# 10BASE-T1L.net
KiCad netlist of a schematic drawn in EAGLE
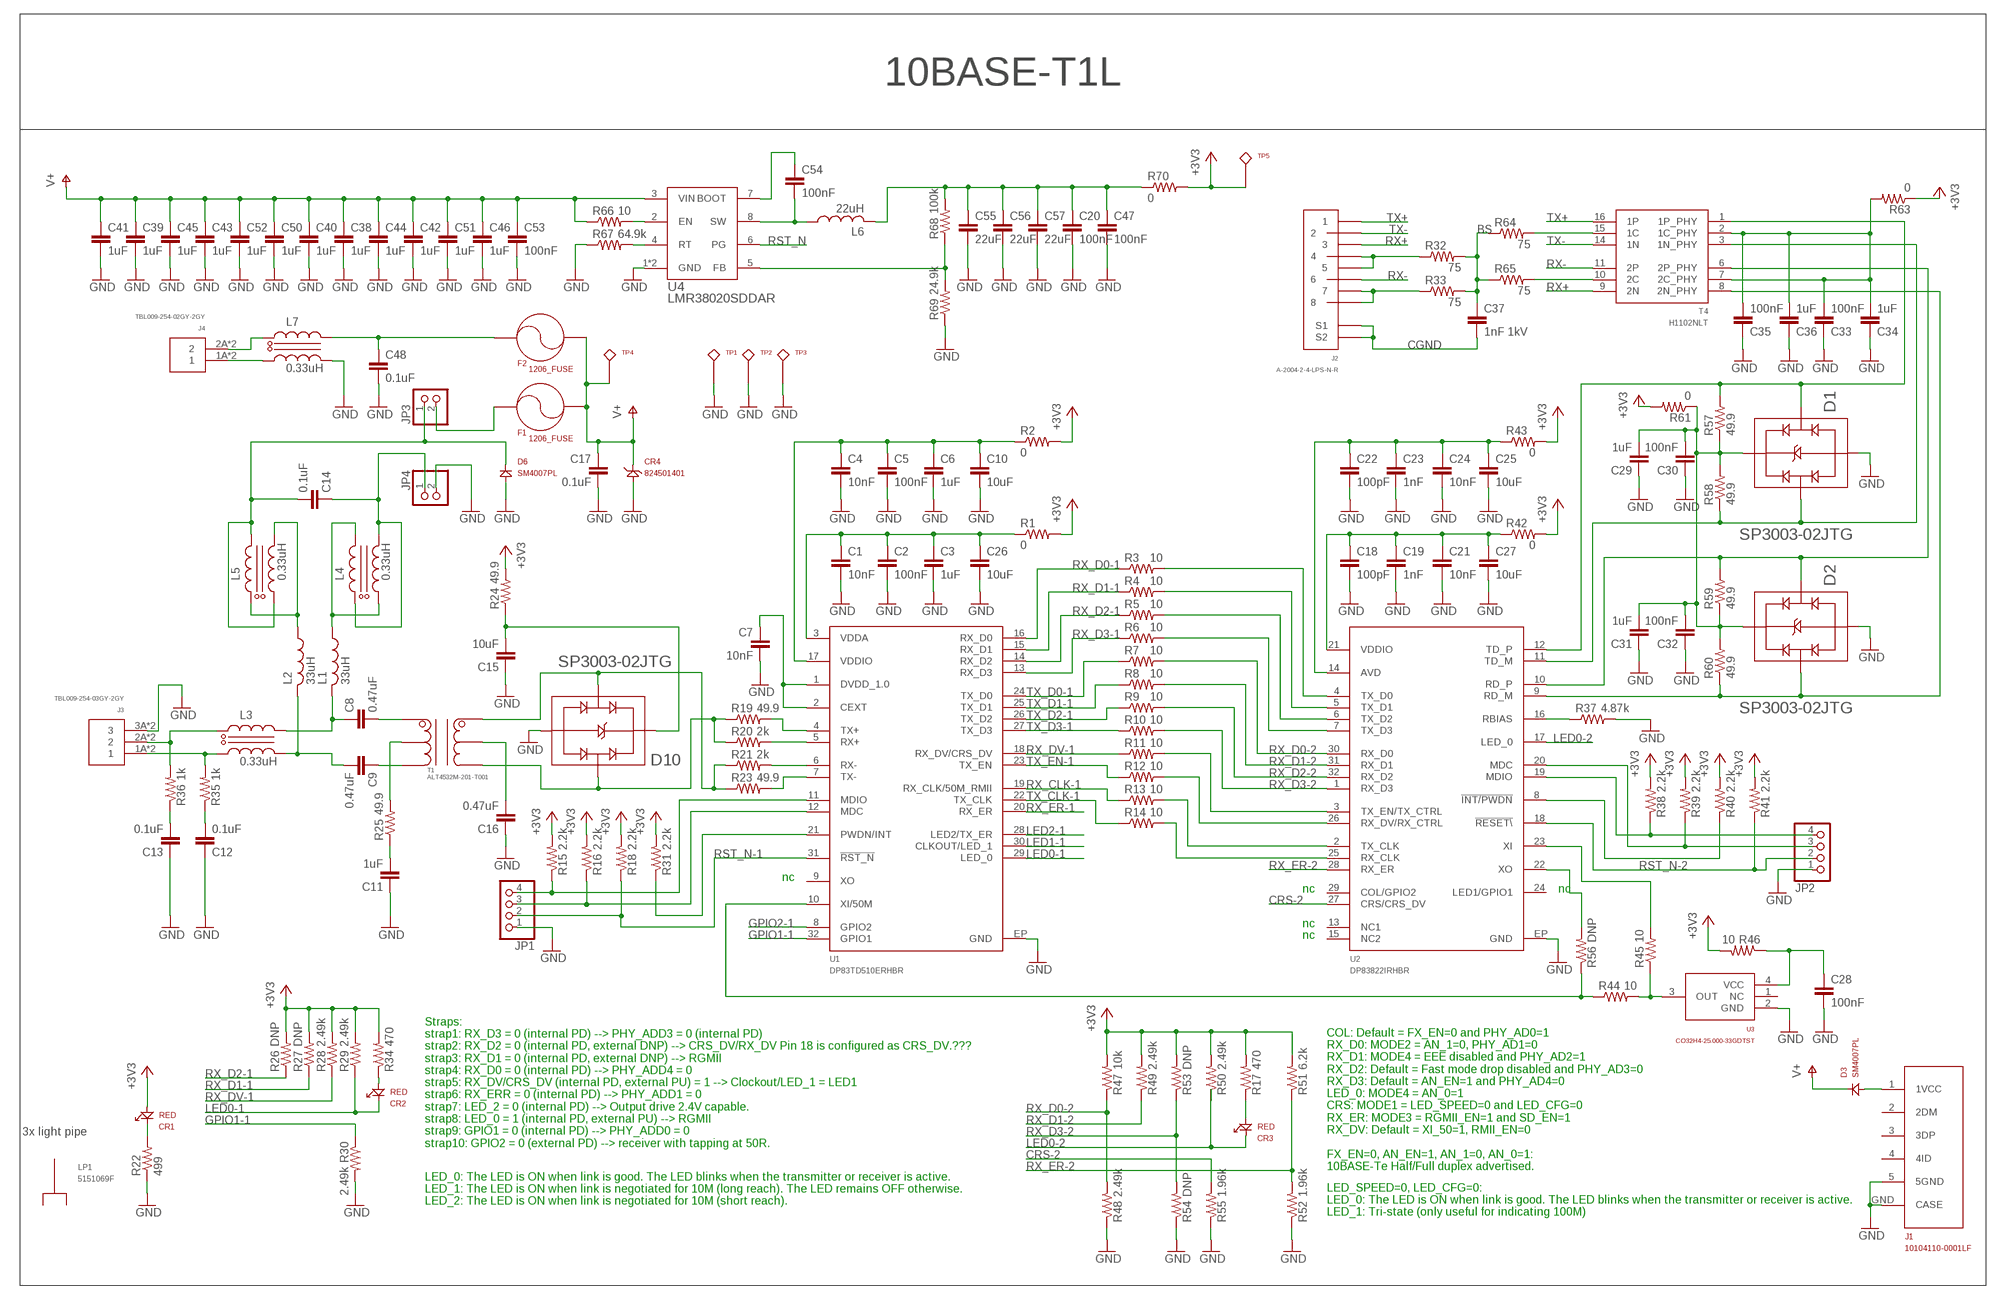
[diagram p0: schematic, sheet 1]

(export (version "E")
  (design (tool "Eeschema 10.0.6"))
  (components
    (comp (ref "C1")
      (value "10nF")
      (footprint "eagle-import:0603")
      (libsource (lib "eagle-import") (part "0603_CAPACITOR"))
    )
    (comp (ref "C2")
      (value "100nF")
      (footprint "eagle-import:0603")
      (libsource (lib "eagle-import") (part "0603_CAPACITOR"))
    )
    (comp (ref "C3")
      (value "1uF")
      (footprint "eagle-import:0603")
      (libsource (lib "eagle-import") (part "0603_CAPACITOR"))
    )
    (comp (ref "C4")
      (value "10nF")
      (footprint "eagle-import:0603")
      (libsource (lib "eagle-import") (part "0603_CAPACITOR"))
    )
    (comp (ref "C5")
      (value "100nF")
      (footprint "eagle-import:0603")
      (libsource (lib "eagle-import") (part "0603_CAPACITOR"))
    )
    (comp (ref "C6")
      (value "1uF")
      (footprint "eagle-import:0603")
      (libsource (lib "eagle-import") (part "0603_CAPACITOR"))
    )
    (comp (ref "C7")
      (value "10nF")
      (footprint "eagle-import:0603")
      (libsource (lib "eagle-import") (part "0603_CAPACITOR"))
    )
    (comp (ref "C8")
      (value "0.47uF")
      (footprint "eagle-import:0603")
      (libsource (lib "eagle-import") (part "0603_CAPACITOR"))
    )
    (comp (ref "C9")
      (value "0.47uF")
      (footprint "eagle-import:0603")
      (libsource (lib "eagle-import") (part "0603_CAPACITOR"))
    )
    (comp (ref "C10")
      (value "10uF")
      (footprint "eagle-import:0805")
      (libsource (lib "eagle-import") (part "0805_CAPACITOR"))
    )
    (comp (ref "C11")
      (value "1uF")
      (footprint "eagle-import:0603")
      (libsource (lib "eagle-import") (part "0603_CAPACITOR"))
    )
    (comp (ref "C12")
      (value "0.1uF")
      (footprint "eagle-import:0603")
      (libsource (lib "eagle-import") (part "0603_CAPACITOR"))
    )
    (comp (ref "C13")
      (value "0.1uF")
      (footprint "eagle-import:0603")
      (libsource (lib "eagle-import") (part "0603_CAPACITOR"))
    )
    (comp (ref "C14")
      (value "0.1uF")
      (footprint "eagle-import:0603")
      (libsource (lib "eagle-import") (part "0603_CAPACITOR"))
    )
    (comp (ref "C15")
      (value "10uF")
      (footprint "eagle-import:0603")
      (libsource (lib "eagle-import") (part "0603_CAPACITOR"))
    )
    (comp (ref "C16")
      (value "0.47uF")
      (footprint "eagle-import:0603")
      (libsource (lib "eagle-import") (part "0603_CAPACITOR"))
    )
    (comp (ref "C17")
      (value "0.1uF")
      (footprint "eagle-import:0603")
      (libsource (lib "eagle-import") (part "0603_CAPACITOR"))
    )
    (comp (ref "C18")
      (value "100pF")
      (footprint "eagle-import:0603")
      (libsource (lib "eagle-import") (part "0603_CAPACITOR"))
    )
    (comp (ref "C19")
      (value "1nF")
      (footprint "eagle-import:0603")
      (libsource (lib "eagle-import") (part "0603_CAPACITOR"))
    )
    (comp (ref "C20")
      (value "100nF")
      (footprint "eagle-import:0603")
      (libsource (lib "eagle-import") (part "0603_CAPACITOR"))
    )
    (comp (ref "C21")
      (value "10nF")
      (footprint "eagle-import:0603")
      (libsource (lib "eagle-import") (part "0603_CAPACITOR"))
    )
    (comp (ref "C22")
      (value "100pF")
      (footprint "eagle-import:0603")
      (libsource (lib "eagle-import") (part "0603_CAPACITOR"))
    )
    (comp (ref "C23")
      (value "1nF")
      (footprint "eagle-import:0603")
      (libsource (lib "eagle-import") (part "0603_CAPACITOR"))
    )
    (comp (ref "C24")
      (value "10nF")
      (footprint "eagle-import:0603")
      (libsource (lib "eagle-import") (part "0603_CAPACITOR"))
    )
    (comp (ref "C25")
      (value "10uF")
      (footprint "eagle-import:0805")
      (libsource (lib "eagle-import") (part "0805_CAPACITOR"))
    )
    (comp (ref "C26")
      (value "10uF")
      (footprint "eagle-import:0805")
      (libsource (lib "eagle-import") (part "0805_CAPACITOR"))
    )
    (comp (ref "C27")
      (value "10uF")
      (footprint "eagle-import:0805")
      (libsource (lib "eagle-import") (part "0805_CAPACITOR"))
    )
    (comp (ref "C28")
      (value "100nF")
      (footprint "eagle-import:0603")
      (libsource (lib "eagle-import") (part "0603_CAPACITOR"))
    )
    (comp (ref "C29")
      (value "1uF")
      (footprint "eagle-import:0603")
      (libsource (lib "eagle-import") (part "0603_CAPACITOR"))
    )
    (comp (ref "C30")
      (value "100nF")
      (footprint "eagle-import:0603")
      (libsource (lib "eagle-import") (part "0603_CAPACITOR"))
    )
    (comp (ref "C31")
      (value "1uF")
      (footprint "eagle-import:0603")
      (libsource (lib "eagle-import") (part "0603_CAPACITOR"))
    )
    (comp (ref "C32")
      (value "100nF")
      (footprint "eagle-import:0603")
      (libsource (lib "eagle-import") (part "0603_CAPACITOR"))
    )
    (comp (ref "C33")
      (value "100nF")
      (footprint "eagle-import:0603")
      (libsource (lib "eagle-import") (part "0603_CAPACITOR"))
    )
    (comp (ref "C34")
      (value "1uF")
      (footprint "eagle-import:0603")
      (libsource (lib "eagle-import") (part "0603_CAPACITOR"))
    )
    (comp (ref "C35")
      (value "100nF")
      (footprint "eagle-import:0603")
      (libsource (lib "eagle-import") (part "0603_CAPACITOR"))
    )
    (comp (ref "C36")
      (value "1uF")
      (footprint "eagle-import:0603")
      (libsource (lib "eagle-import") (part "0603_CAPACITOR"))
    )
    (comp (ref "C37")
      (value "1nF 1kV")
      (footprint "eagle-import:C1206")
      (libsource (lib "eagle-import") (part "C-EUC1206"))
    )
    (comp (ref "C38")
      (value "1uF")
      (footprint "eagle-import:C1206")
      (libsource (lib "eagle-import") (part "C-EUC1206"))
    )
    (comp (ref "C39")
      (value "1uF")
      (footprint "eagle-import:C1206")
      (libsource (lib "eagle-import") (part "C-EUC1206"))
    )
    (comp (ref "C40")
      (value "1uF")
      (footprint "eagle-import:C1206")
      (libsource (lib "eagle-import") (part "C-EUC1206"))
    )
    (comp (ref "C41")
      (value "1uF")
      (footprint "eagle-import:C1206")
      (libsource (lib "eagle-import") (part "C-EUC1206"))
    )
    (comp (ref "C42")
      (value "1uF")
      (footprint "eagle-import:C1206")
      (libsource (lib "eagle-import") (part "C-EUC1206"))
    )
    (comp (ref "C43")
      (value "1uF")
      (footprint "eagle-import:C1206")
      (libsource (lib "eagle-import") (part "C-EUC1206"))
    )
    (comp (ref "C44")
      (value "1uF")
      (footprint "eagle-import:C1206")
      (libsource (lib "eagle-import") (part "C-EUC1206"))
    )
    (comp (ref "C45")
      (value "1uF")
      (footprint "eagle-import:C1206")
      (libsource (lib "eagle-import") (part "C-EUC1206"))
    )
    (comp (ref "C46")
      (value "1uF")
      (footprint "eagle-import:C1206")
      (libsource (lib "eagle-import") (part "C-EUC1206"))
    )
    (comp (ref "C47")
      (value "100nF")
      (footprint "eagle-import:0603")
      (libsource (lib "eagle-import") (part "0603_CAPACITOR"))
    )
    (comp (ref "C48")
      (value "0.1uF")
      (footprint "eagle-import:0603")
      (libsource (lib "eagle-import") (part "0603_CAPACITOR"))
    )
    (comp (ref "C50")
      (value "1uF")
      (footprint "eagle-import:C1206")
      (libsource (lib "eagle-import") (part "C-EUC1206"))
    )
    (comp (ref "C51")
      (value "1uF")
      (footprint "eagle-import:C1206")
      (libsource (lib "eagle-import") (part "C-EUC1206"))
    )
    (comp (ref "C52")
      (value "1uF")
      (footprint "eagle-import:C1206")
      (libsource (lib "eagle-import") (part "C-EUC1206"))
    )
    (comp (ref "C53")
      (value "100nF")
      (footprint "eagle-import:0603")
      (libsource (lib "eagle-import") (part "0603_CAPACITOR"))
    )
    (comp (ref "C54")
      (value "100nF")
      (footprint "eagle-import:0603")
      (libsource (lib "eagle-import") (part "0603_CAPACITOR"))
    )
    (comp (ref "C55")
      (value "22uF")
      (footprint "eagle-import:C1206")
      (libsource (lib "eagle-import") (part "C-EUC1206"))
    )
    (comp (ref "C56")
      (value "22uF")
      (footprint "eagle-import:C1206")
      (libsource (lib "eagle-import") (part "C-EUC1206"))
    )
    (comp (ref "C57")
      (value "22uF")
      (footprint "eagle-import:C1206")
      (libsource (lib "eagle-import") (part "C-EUC1206"))
    )
    (comp (ref "CR1")
      (value "RED")
      (footprint "eagle-import:0603_DIODE")
      (fields (field (name "PARTNO") "732-4978-1-ND"))
      (libsource (lib "eagle-import") (part "150060RS75000"))
    )
    (comp (ref "CR2")
      (value "RED")
      (footprint "eagle-import:0603_DIODE")
      (fields (field (name "PARTNO") "732-4978-1-ND"))
      (libsource (lib "eagle-import") (part "150060RS75000"))
    )
    (comp (ref "CR3")
      (value "RED")
      (footprint "eagle-import:0603_DIODE")
      (fields (field (name "PARTNO") "732-4978-1-ND"))
      (libsource (lib "eagle-import") (part "150060RS75000"))
    )
    (comp (ref "CR4")
      (value "824501401")
      (footprint "eagle-import:DO-214AC")
      (fields (field (name "PARTNO") "732-9960-1-ND"))
      (libsource (lib "eagle-import") (part "824501401"))
    )
    (comp (ref "D1")
      (value "SP3003-02JTG")
      (footprint "eagle-import:SC-70-5")
      (fields (field (name "PARTNO") "F3301CT-ND"))
      (libsource (lib "eagle-import") (part "SP3003-02JTG"))
    )
    (comp (ref "D2")
      (value "SP3003-02JTG")
      (footprint "eagle-import:SC-70-5")
      (fields (field (name "PARTNO") "F3301CT-ND"))
      (libsource (lib "eagle-import") (part "SP3003-02JTG"))
    )
    (comp (ref "D3")
      (value "SM4007PL")
      (footprint "eagle-import:SOD123(AK)")
      (libsource (lib "eagle-import") (part "SM4007PL"))
    )
    (comp (ref "D6")
      (value "SM4007PL")
      (footprint "eagle-import:SOD123(AK)")
      (libsource (lib "eagle-import") (part "SM4007PL"))
    )
    (comp (ref "D10")
      (value "SP3003-02JTG")
      (footprint "eagle-import:SC-70-5")
      (fields (field (name "PARTNO") "F3301CT-ND"))
      (libsource (lib "eagle-import") (part "SP3003-02JTG"))
    )
    (comp (ref "F1")
      (value "1206_FUSE")
      (footprint "eagle-import:1206")
      (libsource (lib "eagle-import") (part "1206_FUSE"))
    )
    (comp (ref "F2")
      (value "1206_FUSE")
      (footprint "eagle-import:1206")
      (libsource (lib "eagle-import") (part "1206_FUSE"))
    )
    (comp (ref "J1")
      (value "10104110-0001LF")
      (footprint "eagle-import:MICRO_USB")
      (fields (field (name "PARTNO") "609-4052-1-ND"))
      (libsource (lib "eagle-import") (part "10104110-0001LF"))
    )
    (comp (ref "J2")
      (value "A-2004-2-4-LPS-N-R")
      (footprint "eagle-import:A-2004-2-4-LPS-N-R")
      (fields (field (name "PARTNO") "AE10387-ND"))
      (libsource (lib "eagle-import") (part "A-2004-2-4-LPS-N-R"))
    )
    (comp (ref "J3")
      (value "TBL009-254-03GY-2GY")
      (footprint "eagle-import:TBL009-254-03GY-2GY")
      (fields (field (name "PARTNO") "102-TBL009-254-03GY-2GY-ND"))
      (libsource (lib "eagle-import") (part "TBL009-254-03GY-2GY"))
    )
    (comp (ref "J4")
      (value "TBL009-254-02GY-2GY")
      (footprint "eagle-import:TBL009-254-02GY-2GY")
      (fields (field (name "PARTNO") "102-TBL009-254-02GY-2GY-ND"))
      (libsource (lib "eagle-import") (part "TBL009-254-02GY-2GY"))
    )
    (comp (ref "JP1")
      (value "PINHD-1X4")
      (footprint "eagle-import:1X04")
      (libsource (lib "eagle-import") (part "PINHD-1X4"))
    )
    (comp (ref "JP2")
      (value "PINHD-1X4")
      (footprint "eagle-import:1X04")
      (libsource (lib "eagle-import") (part "PINHD-1X4"))
    )
    (comp (ref "JP3")
      (value "PINHD-1X2")
      (footprint "eagle-import:1X02")
      (libsource (lib "eagle-import") (part "PINHD-1X2"))
    )
    (comp (ref "JP4")
      (value "PINHD-1X2")
      (footprint "eagle-import:1X02")
      (libsource (lib "eagle-import") (part "PINHD-1X2"))
    )
    (comp (ref "L1")
      (value "33uH")
      (footprint "eagle-import:0806")
      (libsource (lib "eagle-import") (part "FWP201610P-R33ML"))
    )
    (comp (ref "L2")
      (value "33uH")
      (footprint "eagle-import:0806")
      (libsource (lib "eagle-import") (part "FWP201610P-R33ML"))
    )
    (comp (ref "L3")
      (value "0.33uH")
      (footprint "eagle-import:SDCW2520")
      (libsource (lib "eagle-import") (part "SDCW2520S-2-601TF"))
    )
    (comp (ref "L4")
      (value "0.33uH")
      (footprint "eagle-import:SDCW2520")
      (libsource (lib "eagle-import") (part "SDCW2520S-2-601TF"))
    )
    (comp (ref "L5")
      (value "0.33uH")
      (footprint "eagle-import:SDCW2520")
      (libsource (lib "eagle-import") (part "SDCW2520S-2-601TF"))
    )
    (comp (ref "L6")
      (value "22uH")
      (footprint "eagle-import:APW12A10")
      (libsource (lib "eagle-import") (part "APW12A10"))
    )
    (comp (ref "L7")
      (value "0.33uH")
      (footprint "eagle-import:SDCW2520")
      (libsource (lib "eagle-import") (part "SDCW2520S-2-601TF"))
    )
    (comp (ref "LP1")
      (value "5151069F")
      (footprint "eagle-import:5151069F")
      (fields (field (name "PARTNO") "350-2182-ND"))
      (libsource (lib "eagle-import") (part "5151069F"))
    )
    (comp (ref "R1")
      (value "0")
      (footprint "eagle-import:0603")
      (libsource (lib "eagle-import") (part "0603_RESISTOR"))
    )
    (comp (ref "R2")
      (value "0")
      (footprint "eagle-import:0603")
      (libsource (lib "eagle-import") (part "0603_RESISTOR"))
    )
    (comp (ref "R3")
      (value "10")
      (footprint "eagle-import:0603")
      (libsource (lib "eagle-import") (part "0603_RESISTOR"))
    )
    (comp (ref "R4")
      (value "10")
      (footprint "eagle-import:0603")
      (libsource (lib "eagle-import") (part "0603_RESISTOR"))
    )
    (comp (ref "R5")
      (value "10")
      (footprint "eagle-import:0603")
      (libsource (lib "eagle-import") (part "0603_RESISTOR"))
    )
    (comp (ref "R6")
      (value "10")
      (footprint "eagle-import:0603")
      (libsource (lib "eagle-import") (part "0603_RESISTOR"))
    )
    (comp (ref "R7")
      (value "10")
      (footprint "eagle-import:0603")
      (libsource (lib "eagle-import") (part "0603_RESISTOR"))
    )
    (comp (ref "R8")
      (value "10")
      (footprint "eagle-import:0603")
      (libsource (lib "eagle-import") (part "0603_RESISTOR"))
    )
    (comp (ref "R9")
      (value "10")
      (footprint "eagle-import:0603")
      (libsource (lib "eagle-import") (part "0603_RESISTOR"))
    )
    (comp (ref "R10")
      (value "10")
      (footprint "eagle-import:0603")
      (libsource (lib "eagle-import") (part "0603_RESISTOR"))
    )
    (comp (ref "R11")
      (value "10")
      (footprint "eagle-import:0603")
      (libsource (lib "eagle-import") (part "0603_RESISTOR"))
    )
    (comp (ref "R12")
      (value "10")
      (footprint "eagle-import:0603")
      (libsource (lib "eagle-import") (part "0603_RESISTOR"))
    )
    (comp (ref "R13")
      (value "10")
      (footprint "eagle-import:0603")
      (libsource (lib "eagle-import") (part "0603_RESISTOR"))
    )
    (comp (ref "R14")
      (value "10")
      (footprint "eagle-import:0603")
      (libsource (lib "eagle-import") (part "0603_RESISTOR"))
    )
    (comp (ref "R15")
      (value "2.2k")
      (footprint "eagle-import:0603")
      (libsource (lib "eagle-import") (part "0603_RESISTOR"))
    )
    (comp (ref "R16")
      (value "2.2k")
      (footprint "eagle-import:0603")
      (libsource (lib "eagle-import") (part "0603_RESISTOR"))
    )
    (comp (ref "R17")
      (value "470")
      (footprint "eagle-import:0603")
      (libsource (lib "eagle-import") (part "0603_RESISTOR"))
    )
    (comp (ref "R18")
      (value "2.2k")
      (footprint "eagle-import:0603")
      (libsource (lib "eagle-import") (part "0603_RESISTOR"))
    )
    (comp (ref "R19")
      (value "49.9")
      (footprint "eagle-import:0603")
      (libsource (lib "eagle-import") (part "0603_RESISTOR"))
    )
    (comp (ref "R20")
      (value "2k")
      (footprint "eagle-import:0603")
      (libsource (lib "eagle-import") (part "0603_RESISTOR"))
    )
    (comp (ref "R21")
      (value "2k")
      (footprint "eagle-import:0603")
      (libsource (lib "eagle-import") (part "0603_RESISTOR"))
    )
    (comp (ref "R22")
      (value "499")
      (footprint "eagle-import:0603")
      (libsource (lib "eagle-import") (part "0603_RESISTOR"))
    )
    (comp (ref "R23")
      (value "49.9")
      (footprint "eagle-import:0603")
      (libsource (lib "eagle-import") (part "0603_RESISTOR"))
    )
    (comp (ref "R24")
      (value "49.9")
      (footprint "eagle-import:0603")
      (libsource (lib "eagle-import") (part "0603_RESISTOR"))
    )
    (comp (ref "R25")
      (value "49.9")
      (footprint "eagle-import:0603")
      (libsource (lib "eagle-import") (part "0603_RESISTOR"))
    )
    (comp (ref "R26")
      (value "DNP")
      (footprint "eagle-import:0603")
      (libsource (lib "eagle-import") (part "0603_RESISTOR"))
    )
    (comp (ref "R27")
      (value "DNP")
      (footprint "eagle-import:0603")
      (libsource (lib "eagle-import") (part "0603_RESISTOR"))
    )
    (comp (ref "R28")
      (value "2.49k")
      (footprint "eagle-import:0603")
      (libsource (lib "eagle-import") (part "0603_RESISTOR"))
    )
    (comp (ref "R29")
      (value "2.49k")
      (footprint "eagle-import:0603")
      (libsource (lib "eagle-import") (part "0603_RESISTOR"))
    )
    (comp (ref "R30")
      (value "2.49k")
      (footprint "eagle-import:0603")
      (libsource (lib "eagle-import") (part "0603_RESISTOR"))
    )
    (comp (ref "R31")
      (value "2.2k")
      (footprint "eagle-import:0603")
      (libsource (lib "eagle-import") (part "0603_RESISTOR"))
    )
    (comp (ref "R32")
      (value "75")
      (footprint "eagle-import:0603")
      (libsource (lib "eagle-import") (part "0603_RESISTOR"))
    )
    (comp (ref "R33")
      (value "75")
      (footprint "eagle-import:0603")
      (libsource (lib "eagle-import") (part "0603_RESISTOR"))
    )
    (comp (ref "R34")
      (value "470")
      (footprint "eagle-import:0603")
      (libsource (lib "eagle-import") (part "0603_RESISTOR"))
    )
    (comp (ref "R35")
      (value "1k")
      (footprint "eagle-import:0603")
      (libsource (lib "eagle-import") (part "0603_RESISTOR"))
    )
    (comp (ref "R36")
      (value "1k")
      (footprint "eagle-import:0603")
      (libsource (lib "eagle-import") (part "0603_RESISTOR"))
    )
    (comp (ref "R37")
      (value "4.87k")
      (footprint "eagle-import:0603")
      (libsource (lib "eagle-import") (part "0603_RESISTOR"))
    )
    (comp (ref "R38")
      (value "2.2k")
      (footprint "eagle-import:0603")
      (libsource (lib "eagle-import") (part "0603_RESISTOR"))
    )
    (comp (ref "R39")
      (value "2.2k")
      (footprint "eagle-import:0603")
      (libsource (lib "eagle-import") (part "0603_RESISTOR"))
    )
    (comp (ref "R40")
      (value "2.2k")
      (footprint "eagle-import:0603")
      (libsource (lib "eagle-import") (part "0603_RESISTOR"))
    )
    (comp (ref "R41")
      (value "2.2k")
      (footprint "eagle-import:0603")
      (libsource (lib "eagle-import") (part "0603_RESISTOR"))
    )
    (comp (ref "R42")
      (value "0")
      (footprint "eagle-import:0603")
      (libsource (lib "eagle-import") (part "0603_RESISTOR"))
    )
    (comp (ref "R43")
      (value "0")
      (footprint "eagle-import:0603")
      (libsource (lib "eagle-import") (part "0603_RESISTOR"))
    )
    (comp (ref "R44")
      (value "10")
      (footprint "eagle-import:0603")
      (libsource (lib "eagle-import") (part "0603_RESISTOR"))
    )
    (comp (ref "R45")
      (value "10")
      (footprint "eagle-import:0603")
      (libsource (lib "eagle-import") (part "0603_RESISTOR"))
    )
    (comp (ref "R46")
      (value "10")
      (footprint "eagle-import:0603")
      (libsource (lib "eagle-import") (part "0603_RESISTOR"))
    )
    (comp (ref "R47")
      (value "10k")
      (footprint "eagle-import:0603")
      (libsource (lib "eagle-import") (part "0603_RESISTOR"))
    )
    (comp (ref "R48")
      (value "2.49k")
      (footprint "eagle-import:0603")
      (libsource (lib "eagle-import") (part "0603_RESISTOR"))
    )
    (comp (ref "R49")
      (value "2.49k")
      (footprint "eagle-import:0603")
      (libsource (lib "eagle-import") (part "0603_RESISTOR"))
    )
    (comp (ref "R50")
      (value "2.49k")
      (footprint "eagle-import:0603")
      (libsource (lib "eagle-import") (part "0603_RESISTOR"))
    )
    (comp (ref "R51")
      (value "6.2k")
      (footprint "eagle-import:0603")
      (libsource (lib "eagle-import") (part "0603_RESISTOR"))
    )
    (comp (ref "R52")
      (value "1.96k")
      (footprint "eagle-import:0603")
      (libsource (lib "eagle-import") (part "0603_RESISTOR"))
    )
    (comp (ref "R53")
      (value "DNP")
      (footprint "eagle-import:0603")
      (libsource (lib "eagle-import") (part "0603_RESISTOR"))
    )
    (comp (ref "R54")
      (value "DNP")
      (footprint "eagle-import:0603")
      (libsource (lib "eagle-import") (part "0603_RESISTOR"))
    )
    (comp (ref "R55")
      (value "1.96k")
      (footprint "eagle-import:0603")
      (libsource (lib "eagle-import") (part "0603_RESISTOR"))
    )
    (comp (ref "R56")
      (value "DNP")
      (footprint "eagle-import:0603")
      (libsource (lib "eagle-import") (part "0603_RESISTOR"))
    )
    (comp (ref "R57")
      (value "49.9")
      (footprint "eagle-import:0603")
      (libsource (lib "eagle-import") (part "0603_RESISTOR"))
    )
    (comp (ref "R58")
      (value "49.9")
      (footprint "eagle-import:0603")
      (libsource (lib "eagle-import") (part "0603_RESISTOR"))
    )
    (comp (ref "R59")
      (value "49.9")
      (footprint "eagle-import:0603")
      (libsource (lib "eagle-import") (part "0603_RESISTOR"))
    )
    (comp (ref "R60")
      (value "49.9")
      (footprint "eagle-import:0603")
      (libsource (lib "eagle-import") (part "0603_RESISTOR"))
    )
    (comp (ref "R61")
      (value "0")
      (footprint "eagle-import:0603")
      (libsource (lib "eagle-import") (part "0603_RESISTOR"))
    )
    (comp (ref "R63")
      (value "0")
      (footprint "eagle-import:0603")
      (libsource (lib "eagle-import") (part "0603_RESISTOR"))
    )
    (comp (ref "R64")
      (value "75")
      (footprint "eagle-import:0603")
      (libsource (lib "eagle-import") (part "0603_RESISTOR"))
    )
    (comp (ref "R65")
      (value "75")
      (footprint "eagle-import:0603")
      (libsource (lib "eagle-import") (part "0603_RESISTOR"))
    )
    (comp (ref "R66")
      (value "10")
      (footprint "eagle-import:0603")
      (libsource (lib "eagle-import") (part "0603_RESISTOR"))
    )
    (comp (ref "R67")
      (value "64.9k")
      (footprint "eagle-import:0603")
      (libsource (lib "eagle-import") (part "0603_RESISTOR"))
    )
    (comp (ref "R68")
      (value "100k")
      (footprint "eagle-import:0603")
      (libsource (lib "eagle-import") (part "0603_RESISTOR"))
    )
    (comp (ref "R69")
      (value "24.9k")
      (footprint "eagle-import:0603")
      (libsource (lib "eagle-import") (part "0603_RESISTOR"))
    )
    (comp (ref "R70")
      (value "0")
      (footprint "eagle-import:0603")
      (libsource (lib "eagle-import") (part "0603_RESISTOR"))
    )
    (comp (ref "T1")
      (value "ALT4532M-201-T001")
      (footprint "eagle-import:TDK_ALT")
      (fields (field (name "PARTNO") "445-15085-1-ND"))
      (libsource (lib "eagle-import") (part "ALT4532M-201-T001"))
    )
    (comp (ref "T4")
      (value "H1102NLT")
      (footprint "eagle-import:H1102NLT")
      (libsource (lib "eagle-import") (part "H1102NLT"))
    )
    (comp (ref "TP1")
      (value "5011")
      (footprint "eagle-import:5010")
      (fields (field (name "PARTNO") "36-5011-ND"))
      (libsource (lib "eagle-import") (part "5011"))
    )
    (comp (ref "TP2")
      (value "5011")
      (footprint "eagle-import:5010")
      (fields (field (name "PARTNO") "36-5011-ND"))
      (libsource (lib "eagle-import") (part "5011"))
    )
    (comp (ref "TP3")
      (value "5011")
      (footprint "eagle-import:5010")
      (fields (field (name "PARTNO") "36-5011-ND"))
      (libsource (lib "eagle-import") (part "5011"))
    )
    (comp (ref "TP4")
      (value "5010")
      (footprint "eagle-import:5010")
      (fields (field (name "PARTNO") "36-5010-ND"))
      (libsource (lib "eagle-import") (part "5010"))
    )
    (comp (ref "TP5")
      (value "5010")
      (footprint "eagle-import:5010")
      (fields (field (name "PARTNO") "36-5010-ND"))
      (libsource (lib "eagle-import") (part "5010"))
    )
    (comp (ref "U1")
      (value "DP83TD510ERHBR")
      (footprint "eagle-import:QFN32-55_TI")
      (fields (field (name "PARTNO") "296-DP83TD510ERHBRCT-ND"))
      (libsource (lib "eagle-import") (part "DP83TD510ERHBR"))
    )
    (comp (ref "U2")
      (value "DP83822IRHBR")
      (footprint "eagle-import:QFN32-55_TI")
      (fields (field (name "PARTNO") "296-44794-1-ND"))
      (libsource (lib "eagle-import") (part "DP83822IRHBR"))
    )
    (comp (ref "U3")
      (value "CO32H4-25.000-33GDTST")
      (footprint "eagle-import:3.2X2.5_4SMD")
      (libsource (lib "eagle-import") (part "CO32H4-25.000-33GDTST"))
    )
    (comp (ref "U4")
      (value "LMR38020SDDAR")
      (footprint "eagle-import:SOIC8_TP_TI")
      (fields (field (name "PARTNO") "296-LMR38020SDDARCT-ND"))
      (libsource (lib "eagle-import") (part "LMR38020SDDAR"))
    )
  )
  (nets
    (net (code "1") (name "+3V3") (class "Default")
      (node (ref "CR1") (pin "A") (pinfunction "A_A") (pintype "bidirectional"))
      (node (ref "R1") (pin "2") (pinfunction "2_2") (pintype "passive"))
      (node (ref "R15") (pin "2") (pinfunction "2_2") (pintype "passive"))
      (node (ref "R16") (pin "2") (pinfunction "2_2") (pintype "passive"))
      (node (ref "R17") (pin "2") (pinfunction "2_2") (pintype "passive"))
      (node (ref "R18") (pin "2") (pinfunction "2_2") (pintype "passive"))
      (node (ref "R2") (pin "2") (pinfunction "2_2") (pintype "passive"))
      (node (ref "R24") (pin "2") (pinfunction "2_2") (pintype "passive"))
      (node (ref "R26") (pin "2") (pinfunction "2_2") (pintype "passive"))
      (node (ref "R27") (pin "2") (pinfunction "2_2") (pintype "passive"))
      (node (ref "R28") (pin "2") (pinfunction "2_2") (pintype "passive"))
      (node (ref "R29") (pin "2") (pinfunction "2_2") (pintype "passive"))
      (node (ref "R31") (pin "2") (pinfunction "2_2") (pintype "passive"))
      (node (ref "R34") (pin "2") (pinfunction "2_2") (pintype "passive"))
      (node (ref "R38") (pin "2") (pinfunction "2_2") (pintype "passive"))
      (node (ref "R39") (pin "2") (pinfunction "2_2") (pintype "passive"))
      (node (ref "R40") (pin "2") (pinfunction "2_2") (pintype "passive"))
      (node (ref "R41") (pin "2") (pinfunction "2_2") (pintype "passive"))
      (node (ref "R42") (pin "2") (pinfunction "2_2") (pintype "passive"))
      (node (ref "R43") (pin "2") (pinfunction "2_2") (pintype "passive"))
      (node (ref "R46") (pin "2") (pinfunction "2_2") (pintype "passive"))
      (node (ref "R47") (pin "2") (pinfunction "2_2") (pintype "passive"))
      (node (ref "R49") (pin "2") (pinfunction "2_2") (pintype "passive"))
      (node (ref "R50") (pin "2") (pinfunction "2_2") (pintype "passive"))
      (node (ref "R51") (pin "2") (pinfunction "2_2") (pintype "passive"))
      (node (ref "R53") (pin "2") (pinfunction "2_2") (pintype "passive"))
      (node (ref "R61") (pin "2") (pinfunction "2_2") (pintype "passive"))
      (node (ref "R63") (pin "1") (pinfunction "1_1") (pintype "passive"))
      (node (ref "R70") (pin "2") (pinfunction "2_2") (pintype "passive"))
      (node (ref "TP5") (pin "P$1") (pinfunction "P$1_P$1") (pintype "bidirectional"))
    )
    (net (code "2") (name "BS") (class "Default")
      (node (ref "C37") (pin "1") (pinfunction "1_1") (pintype "passive"))
      (node (ref "R32") (pin "2") (pinfunction "2_2") (pintype "passive"))
      (node (ref "R33") (pin "2") (pinfunction "2_2") (pintype "passive"))
      (node (ref "R64") (pin "1") (pinfunction "1_1") (pintype "passive"))
      (node (ref "R65") (pin "1") (pinfunction "1_1") (pintype "passive"))
    )
    (net (code "3") (name "CGND") (class "Default")
      (node (ref "C37") (pin "2") (pinfunction "2_2") (pintype "passive"))
      (node (ref "J2") (pin "S1") (pinfunction "S1_S1") (pintype "bidirectional"))
      (node (ref "J2") (pin "S2") (pinfunction "S2_S2") (pintype "bidirectional"))
    )
    (net (code "4") (name "CRS-2") (class "Default")
      (node (ref "R55") (pin "2") (pinfunction "2_2") (pintype "passive"))
      (node (ref "U2") (pin "27") (pinfunction "CRS/CRS_DV_27") (pintype "bidirectional"))
    )
    (net (code "5") (name "GND") (class "Default")
      (node (ref "C1") (pin "2") (pinfunction "2_2") (pintype "passive"))
      (node (ref "C10") (pin "2") (pinfunction "2_2") (pintype "passive"))
      (node (ref "C11") (pin "1") (pinfunction "1_1") (pintype "passive"))
      (node (ref "C12") (pin "1") (pinfunction "1_1") (pintype "passive"))
      (node (ref "C13") (pin "1") (pinfunction "1_1") (pintype "passive"))
      (node (ref "C15") (pin "1") (pinfunction "1_1") (pintype "passive"))
      (node (ref "C16") (pin "1") (pinfunction "1_1") (pintype "passive"))
      (node (ref "C17") (pin "2") (pinfunction "2_2") (pintype "passive"))
      (node (ref "C18") (pin "2") (pinfunction "2_2") (pintype "passive"))
      (node (ref "C19") (pin "2") (pinfunction "2_2") (pintype "passive"))
      (node (ref "C2") (pin "2") (pinfunction "2_2") (pintype "passive"))
      (node (ref "C20") (pin "2") (pinfunction "2_2") (pintype "passive"))
      (node (ref "C21") (pin "2") (pinfunction "2_2") (pintype "passive"))
      (node (ref "C22") (pin "2") (pinfunction "2_2") (pintype "passive"))
      (node (ref "C23") (pin "2") (pinfunction "2_2") (pintype "passive"))
      (node (ref "C24") (pin "2") (pinfunction "2_2") (pintype "passive"))
      (node (ref "C25") (pin "2") (pinfunction "2_2") (pintype "passive"))
      (node (ref "C26") (pin "2") (pinfunction "2_2") (pintype "passive"))
      (node (ref "C27") (pin "2") (pinfunction "2_2") (pintype "passive"))
      (node (ref "C28") (pin "2") (pinfunction "2_2") (pintype "passive"))
      (node (ref "C29") (pin "1") (pinfunction "1_1") (pintype "passive"))
      (node (ref "C3") (pin "2") (pinfunction "2_2") (pintype "passive"))
      (node (ref "C30") (pin "1") (pinfunction "1_1") (pintype "passive"))
      (node (ref "C31") (pin "1") (pinfunction "1_1") (pintype "passive"))
      (node (ref "C32") (pin "1") (pinfunction "1_1") (pintype "passive"))
      (node (ref "C33") (pin "1") (pinfunction "1_1") (pintype "passive"))
      (node (ref "C34") (pin "1") (pinfunction "1_1") (pintype "passive"))
      (node (ref "C35") (pin "1") (pinfunction "1_1") (pintype "passive"))
      (node (ref "C36") (pin "1") (pinfunction "1_1") (pintype "passive"))
      (node (ref "C38") (pin "2") (pinfunction "2_2") (pintype "passive"))
      (node (ref "C39") (pin "2") (pinfunction "2_2") (pintype "passive"))
      (node (ref "C4") (pin "2") (pinfunction "2_2") (pintype "passive"))
      (node (ref "C40") (pin "2") (pinfunction "2_2") (pintype "passive"))
      (node (ref "C41") (pin "2") (pinfunction "2_2") (pintype "passive"))
      (node (ref "C42") (pin "2") (pinfunction "2_2") (pintype "passive"))
      (node (ref "C43") (pin "2") (pinfunction "2_2") (pintype "passive"))
      (node (ref "C44") (pin "2") (pinfunction "2_2") (pintype "passive"))
      (node (ref "C45") (pin "2") (pinfunction "2_2") (pintype "passive"))
      (node (ref "C46") (pin "2") (pinfunction "2_2") (pintype "passive"))
      (node (ref "C47") (pin "2") (pinfunction "2_2") (pintype "passive"))
      (node (ref "C48") (pin "2") (pinfunction "2_2") (pintype "passive"))
      (node (ref "C5") (pin "2") (pinfunction "2_2") (pintype "passive"))
      (node (ref "C50") (pin "2") (pinfunction "2_2") (pintype "passive"))
      (node (ref "C51") (pin "2") (pinfunction "2_2") (pintype "passive"))
      (node (ref "C52") (pin "2") (pinfunction "2_2") (pintype "passive"))
      (node (ref "C53") (pin "2") (pinfunction "2_2") (pintype "passive"))
      (node (ref "C55") (pin "2") (pinfunction "2_2") (pintype "passive"))
      (node (ref "C56") (pin "2") (pinfunction "2_2") (pintype "passive"))
      (node (ref "C57") (pin "2") (pinfunction "2_2") (pintype "passive"))
      (node (ref "C6") (pin "2") (pinfunction "2_2") (pintype "passive"))
      (node (ref "C7") (pin "2") (pinfunction "2_2") (pintype "passive"))
      (node (ref "CR4") (pin "A") (pinfunction "A_A") (pintype "bidirectional"))
      (node (ref "D1") (pin "2") (pinfunction "GND_2") (pintype "bidirectional"))
      (node (ref "D10") (pin "2") (pinfunction "GND_2") (pintype "bidirectional"))
      (node (ref "D2") (pin "2") (pinfunction "GND_2") (pintype "bidirectional"))
      (node (ref "D6") (pin "A") (pinfunction "A_A") (pintype "bidirectional"))
      (node (ref "J1") (pin "5") (pinfunction "5GND_5") (pintype "bidirectional"))
      (node (ref "J1") (pin "GND") (pinfunction "CASE_GND") (pintype "bidirectional"))
      (node (ref "J3") (pin "3A") (pinfunction "3_3A") (pintype "bidirectional"))
      (node (ref "J3") (pin "3B") (pinfunction "3_3B") (pintype "bidirectional"))
      (node (ref "JP1") (pin "1") (pinfunction "1_1") (pintype "passive"))
      (node (ref "JP2") (pin "1") (pinfunction "1_1") (pintype "passive"))
      (node (ref "JP4") (pin "2") (pinfunction "2_2") (pintype "passive"))
      (node (ref "L7") (pin "B2") (pinfunction "2OUT_B2") (pintype "bidirectional"))
      (node (ref "R22") (pin "1") (pinfunction "1_1") (pintype "passive"))
      (node (ref "R30") (pin "2") (pinfunction "2_2") (pintype "passive"))
      (node (ref "R37") (pin "2") (pinfunction "2_2") (pintype "passive"))
      (node (ref "R48") (pin "1") (pinfunction "1_1") (pintype "passive"))
      (node (ref "R52") (pin "1") (pinfunction "1_1") (pintype "passive"))
      (node (ref "R54") (pin "1") (pinfunction "1_1") (pintype "passive"))
      (node (ref "R55") (pin "1") (pinfunction "1_1") (pintype "passive"))
      (node (ref "R67") (pin "1") (pinfunction "1_1") (pintype "passive"))
      (node (ref "R69") (pin "1") (pinfunction "1_1") (pintype "passive"))
      (node (ref "TP1") (pin "P$1") (pinfunction "P$1_P$1") (pintype "bidirectional"))
      (node (ref "TP2") (pin "P$1") (pinfunction "P$1_P$1") (pintype "bidirectional"))
      (node (ref "TP3") (pin "P$1") (pinfunction "P$1_P$1") (pintype "bidirectional"))
      (node (ref "U1") (pin "EP") (pinfunction "GND_EP") (pintype "bidirectional"))
      (node (ref "U2") (pin "EP") (pinfunction "GND_EP") (pintype "bidirectional"))
      (node (ref "U3") (pin "2") (pinfunction "GND_2") (pintype "bidirectional"))
      (node (ref "U4") (pin "1") (pinfunction "GND_1") (pintype "bidirectional"))
      (node (ref "U4") (pin "TP") (pinfunction "GND_TP") (pintype "bidirectional"))
    )
    (net (code "6") (name "GPIO1-1") (class "Default")
      (node (ref "R30") (pin "1") (pinfunction "1_1") (pintype "passive"))
      (node (ref "U1") (pin "32") (pinfunction "GPIO1_32") (pintype "bidirectional"))
    )
    (net (code "7") (name "GPIO2-1") (class "Default")
      (node (ref "U1") (pin "8") (pinfunction "GPIO2_8") (pintype "bidirectional"))
    )
    (net (code "8") (name "LED0-1") (class "Default")
      (node (ref "CR2") (pin "K") (pinfunction "K_K") (pintype "bidirectional"))
      (node (ref "R29") (pin "1") (pinfunction "1_1") (pintype "passive"))
      (node (ref "U1") (pin "29") (pinfunction "LED_0_29") (pintype "bidirectional"))
    )
    (net (code "9") (name "LED0-2") (class "Default")
      (node (ref "CR3") (pin "K") (pinfunction "K_K") (pintype "bidirectional"))
      (node (ref "R50") (pin "1") (pinfunction "1_1") (pintype "passive"))
      (node (ref "U2") (pin "17") (pinfunction "LED_0_17") (pintype "bidirectional"))
    )
    (net (code "10") (name "LED1-1") (class "Default")
      (node (ref "U1") (pin "30") (pinfunction "CLKOUT/LED_1_30") (pintype "bidirectional"))
    )
    (net (code "11") (name "LED2-1") (class "Default")
      (node (ref "U1") (pin "28") (pinfunction "LED2/TX_ER_28") (pintype "bidirectional"))
    )
    (net (code "12") (name "Net-(C8-Pad2)") (class "Default")
      (node (ref "C8") (pin "2") (pinfunction "2_2") (pintype "passive"))
      (node (ref "T1") (pin "1") (pinfunction "1_1") (pintype "bidirectional"))
    )
    (net (code "13") (name "Net-(C11-Pad2)") (class "Default")
      (node (ref "C11") (pin "2") (pinfunction "2_2") (pintype "passive"))
      (node (ref "R25") (pin "1") (pinfunction "1_1") (pintype "passive"))
    )
    (net (code "14") (name "Net-(C12-Pad2)") (class "Default")
      (node (ref "C12") (pin "2") (pinfunction "2_2") (pintype "passive"))
      (node (ref "R35") (pin "1") (pinfunction "1_1") (pintype "passive"))
    )
    (net (code "15") (name "Net-(C13-Pad2)") (class "Default")
      (node (ref "C13") (pin "2") (pinfunction "2_2") (pintype "passive"))
      (node (ref "R36") (pin "1") (pinfunction "1_1") (pintype "passive"))
    )
    (net (code "16") (name "Net-(CR1-PadK)") (class "Default")
      (node (ref "CR1") (pin "K") (pinfunction "K_K") (pintype "bidirectional"))
      (node (ref "R22") (pin "2") (pinfunction "2_2") (pintype "passive"))
    )
    (net (code "17") (name "Net-(CR2-PadA)") (class "Default")
      (node (ref "CR2") (pin "A") (pinfunction "A_A") (pintype "bidirectional"))
      (node (ref "R34") (pin "1") (pinfunction "1_1") (pintype "passive"))
    )
    (net (code "18") (name "Net-(CR3-PadA)") (class "Default")
      (node (ref "CR3") (pin "A") (pinfunction "A_A") (pintype "bidirectional"))
      (node (ref "R17") (pin "1") (pinfunction "1_1") (pintype "passive"))
    )
    (net (code "19") (name "Net-(D1-IO1)") (class "Default")
      (node (ref "D1") (pin "5") (pinfunction "IO1_5") (pintype "bidirectional"))
      (node (ref "R58") (pin "1") (pinfunction "1_1") (pintype "passive"))
      (node (ref "T4") (pin "3") (pinfunction "1N_PHY_3") (pintype "bidirectional"))
      (node (ref "U2") (pin "11") (pinfunction "TD_M_11") (pintype "bidirectional"))
    )
    (net (code "20") (name "Net-(D1-IO2)") (class "Default")
      (node (ref "D1") (pin "4") (pinfunction "IO2_4") (pintype "bidirectional"))
      (node (ref "R57") (pin "2") (pinfunction "2_2") (pintype "passive"))
      (node (ref "T4") (pin "1") (pinfunction "1P_PHY_1") (pintype "bidirectional"))
      (node (ref "U2") (pin "12") (pinfunction "TD_P_12") (pintype "bidirectional"))
    )
    (net (code "21") (name "Net-(D1-VCC)") (class "Default")
      (node (ref "C29") (pin "2") (pinfunction "2_2") (pintype "passive"))
      (node (ref "C30") (pin "2") (pinfunction "2_2") (pintype "passive"))
      (node (ref "C31") (pin "2") (pinfunction "2_2") (pintype "passive"))
      (node (ref "C32") (pin "2") (pinfunction "2_2") (pintype "passive"))
      (node (ref "D1") (pin "3") (pinfunction "VCC_3") (pintype "bidirectional"))
      (node (ref "D2") (pin "3") (pinfunction "VCC_3") (pintype "bidirectional"))
      (node (ref "R57") (pin "1") (pinfunction "1_1") (pintype "passive"))
      (node (ref "R58") (pin "2") (pinfunction "2_2") (pintype "passive"))
      (node (ref "R59") (pin "1") (pinfunction "1_1") (pintype "passive"))
      (node (ref "R60") (pin "2") (pinfunction "2_2") (pintype "passive"))
      (node (ref "R61") (pin "1") (pinfunction "1_1") (pintype "passive"))
    )
    (net (code "22") (name "Net-(D2-IO1)") (class "Default")
      (node (ref "D2") (pin "5") (pinfunction "IO1_5") (pintype "bidirectional"))
      (node (ref "R60") (pin "1") (pinfunction "1_1") (pintype "passive"))
      (node (ref "T4") (pin "8") (pinfunction "2N_PHY_8") (pintype "bidirectional"))
      (node (ref "U2") (pin "9") (pinfunction "RD_M_9") (pintype "bidirectional"))
    )
    (net (code "23") (name "Net-(D2-IO2)") (class "Default")
      (node (ref "D2") (pin "4") (pinfunction "IO2_4") (pintype "bidirectional"))
      (node (ref "R59") (pin "2") (pinfunction "2_2") (pintype "passive"))
      (node (ref "T4") (pin "6") (pinfunction "2P_PHY_6") (pintype "bidirectional"))
      (node (ref "U2") (pin "10") (pinfunction "RD_P_10") (pintype "bidirectional"))
    )
    (net (code "24") (name "Net-(D10-IO1)") (class "Default")
      (node (ref "D10") (pin "5") (pinfunction "IO1_5") (pintype "bidirectional"))
      (node (ref "R21") (pin "1") (pinfunction "1_1") (pintype "passive"))
      (node (ref "R23") (pin "1") (pinfunction "1_1") (pintype "passive"))
      (node (ref "T1") (pin "5") (pinfunction "6_5") (pintype "bidirectional"))
    )
    (net (code "25") (name "Net-(D10-IO2)") (class "Default")
      (node (ref "D10") (pin "4") (pinfunction "IO2_4") (pintype "bidirectional"))
      (node (ref "R19") (pin "1") (pinfunction "1_1") (pintype "passive"))
      (node (ref "R20") (pin "1") (pinfunction "1_1") (pintype "passive"))
      (node (ref "T1") (pin "4") (pinfunction "4_4") (pintype "bidirectional"))
    )
    (net (code "26") (name "Net-(D10-VCC)") (class "Default")
      (node (ref "C15") (pin "2") (pinfunction "2_2") (pintype "passive"))
      (node (ref "D10") (pin "3") (pinfunction "VCC_3") (pintype "bidirectional"))
      (node (ref "R24") (pin "1") (pinfunction "1_1") (pintype "passive"))
    )
    (net (code "27") (name "Net-(F1-P$1)") (class "Default")
      (node (ref "F1") (pin "1") (pinfunction "P$1_1") (pintype "bidirectional"))
      (node (ref "JP3") (pin "2") (pinfunction "2_2") (pintype "passive"))
    )
    (net (code "28") (name "Net-(F2-P$1)") (class "Default")
      (node (ref "C48") (pin "1") (pinfunction "1_1") (pintype "passive"))
      (node (ref "F2") (pin "1") (pinfunction "P$1_1") (pintype "bidirectional"))
      (node (ref "L7") (pin "A2") (pinfunction "1OUT_A2") (pintype "bidirectional"))
    )
    (net (code "29") (name "Net-(J1-1VCC)") (class "Default")
      (node (ref "D3") (pin "A") (pinfunction "A_A") (pintype "bidirectional"))
      (node (ref "J1") (pin "1") (pinfunction "1VCC_1") (pintype "bidirectional"))
    )
    (net (code "30") (name "Net-(J2-Pad4)") (class "Default")
      (node (ref "J2") (pin "4") (pinfunction "4_4") (pintype "bidirectional"))
      (node (ref "J2") (pin "5") (pinfunction "5_5") (pintype "bidirectional"))
      (node (ref "R32") (pin "1") (pinfunction "1_1") (pintype "passive"))
    )
    (net (code "31") (name "Net-(J2-Pad7)") (class "Default")
      (node (ref "J2") (pin "7") (pinfunction "7_7") (pintype "bidirectional"))
      (node (ref "J2") (pin "8") (pinfunction "8_8") (pintype "bidirectional"))
      (node (ref "R33") (pin "1") (pinfunction "1_1") (pintype "passive"))
    )
    (net (code "32") (name "Net-(L1-1)") (class "Default")
      (node (ref "L1") (pin "P$1") (pinfunction "1_P$1") (pintype "passive"))
      (node (ref "L4") (pin "A2") (pinfunction "1OUT_A2") (pintype "bidirectional"))
      (node (ref "L4") (pin "B1") (pinfunction "2IN_B1") (pintype "bidirectional"))
    )
    (net (code "33") (name "Net-(L1-2)") (class "Default")
      (node (ref "C8") (pin "1") (pinfunction "1_1") (pintype "passive"))
      (node (ref "L1") (pin "P$2") (pinfunction "2_P$2") (pintype "passive"))
      (node (ref "L3") (pin "A2") (pinfunction "1OUT_A2") (pintype "bidirectional"))
    )
    (net (code "34") (name "Net-(L2-1)") (class "Default")
      (node (ref "L2") (pin "P$1") (pinfunction "1_P$1") (pintype "passive"))
      (node (ref "L5") (pin "A1") (pinfunction "1IN_A1") (pintype "bidirectional"))
      (node (ref "L5") (pin "B2") (pinfunction "2OUT_B2") (pintype "bidirectional"))
    )
    (net (code "35") (name "Net-(L2-2)") (class "Default")
      (node (ref "C9") (pin "2") (pinfunction "2_2") (pintype "passive"))
      (node (ref "L2") (pin "P$2") (pinfunction "2_P$2") (pintype "passive"))
      (node (ref "L3") (pin "B2") (pinfunction "2OUT_B2") (pintype "bidirectional"))
    )
    (net (code "36") (name "Net-(L3-1IN)") (class "Default")
      (node (ref "J3") (pin "2A") (pinfunction "2_2A") (pintype "bidirectional"))
      (node (ref "J3") (pin "2B") (pinfunction "2_2B") (pintype "bidirectional"))
      (node (ref "L3") (pin "A1") (pinfunction "1IN_A1") (pintype "bidirectional"))
      (node (ref "R36") (pin "2") (pinfunction "2_2") (pintype "passive"))
    )
    (net (code "37") (name "Net-(L3-2IN)") (class "Default")
      (node (ref "J3") (pin "1A") (pinfunction "1_1A") (pintype "bidirectional"))
      (node (ref "J3") (pin "1B") (pinfunction "1_1B") (pintype "bidirectional"))
      (node (ref "L3") (pin "B1") (pinfunction "2IN_B1") (pintype "bidirectional"))
      (node (ref "R35") (pin "2") (pinfunction "2_2") (pintype "passive"))
    )
    (net (code "38") (name "Net-(L4-1IN)") (class "Default")
      (node (ref "C14") (pin "1") (pinfunction "1_1") (pintype "passive"))
      (node (ref "JP4") (pin "1") (pinfunction "1_1") (pintype "passive"))
      (node (ref "L4") (pin "A1") (pinfunction "1IN_A1") (pintype "bidirectional"))
      (node (ref "L4") (pin "B2") (pinfunction "2OUT_B2") (pintype "bidirectional"))
    )
    (net (code "39") (name "Net-(L5-1OUT)") (class "Default")
      (node (ref "C14") (pin "2") (pinfunction "2_2") (pintype "passive"))
      (node (ref "D6") (pin "K") (pinfunction "K_K") (pintype "bidirectional"))
      (node (ref "JP3") (pin "1") (pinfunction "1_1") (pintype "passive"))
      (node (ref "L5") (pin "A2") (pinfunction "1OUT_A2") (pintype "bidirectional"))
      (node (ref "L5") (pin "B1") (pinfunction "2IN_B1") (pintype "bidirectional"))
    )
    (net (code "40") (name "Net-(L6-1)") (class "Default")
      (node (ref "C54") (pin "2") (pinfunction "2_2") (pintype "passive"))
      (node (ref "L6") (pin "P$1") (pinfunction "1_P$1") (pintype "passive"))
      (node (ref "U4") (pin "8") (pinfunction "SW_8") (pintype "bidirectional"))
    )
    (net (code "41") (name "Net-(L6-2)") (class "Default")
      (node (ref "C20") (pin "1") (pinfunction "1_1") (pintype "passive"))
      (node (ref "C47") (pin "1") (pinfunction "1_1") (pintype "passive"))
      (node (ref "C55") (pin "1") (pinfunction "1_1") (pintype "passive"))
      (node (ref "C56") (pin "1") (pinfunction "1_1") (pintype "passive"))
      (node (ref "C57") (pin "1") (pinfunction "1_1") (pintype "passive"))
      (node (ref "L6") (pin "P$2") (pinfunction "2_P$2") (pintype "passive"))
      (node (ref "R68") (pin "2") (pinfunction "2_2") (pintype "passive"))
      (node (ref "R70") (pin "1") (pinfunction "1_1") (pintype "passive"))
    )
    (net (code "42") (name "Net-(L7-1IN)") (class "Default")
      (node (ref "J4") (pin "2A") (pinfunction "2_2A") (pintype "bidirectional"))
      (node (ref "J4") (pin "2B") (pinfunction "2_2B") (pintype "bidirectional"))
      (node (ref "L7") (pin "A1") (pinfunction "1IN_A1") (pintype "bidirectional"))
    )
    (net (code "43") (name "Net-(L7-2IN)") (class "Default")
      (node (ref "J4") (pin "1A") (pinfunction "1_1A") (pintype "bidirectional"))
      (node (ref "J4") (pin "1B") (pinfunction "1_1B") (pintype "bidirectional"))
      (node (ref "L7") (pin "B1") (pinfunction "2IN_B1") (pintype "bidirectional"))
    )
    (net (code "44") (name "Net-(T1-2)") (class "Default")
      (node (ref "R25") (pin "2") (pinfunction "2_2") (pintype "passive"))
      (node (ref "T1") (pin "6") (pinfunction "2_6") (pintype "bidirectional"))
    )
    (net (code "45") (name "Net-(T1-3)") (class "Default")
      (node (ref "C9") (pin "1") (pinfunction "1_1") (pintype "passive"))
      (node (ref "T1") (pin "2") (pinfunction "3_2") (pintype "bidirectional"))
    )
    (net (code "46") (name "Net-(T1-5)") (class "Default")
      (node (ref "C16") (pin "2") (pinfunction "2_2") (pintype "passive"))
      (node (ref "T1") (pin "3") (pinfunction "5_3") (pintype "bidirectional"))
    )
    (net (code "47") (name "Net-(T4-1C)") (class "Default")
      (node (ref "R64") (pin "2") (pinfunction "2_2") (pintype "passive"))
      (node (ref "T4") (pin "15") (pinfunction "1C_15") (pintype "bidirectional"))
    )
    (net (code "48") (name "Net-(T4-1C_PHY)") (class "Default")
      (node (ref "C33") (pin "2") (pinfunction "2_2") (pintype "passive"))
      (node (ref "C34") (pin "2") (pinfunction "2_2") (pintype "passive"))
      (node (ref "C35") (pin "2") (pinfunction "2_2") (pintype "passive"))
      (node (ref "C36") (pin "2") (pinfunction "2_2") (pintype "passive"))
      (node (ref "R63") (pin "2") (pinfunction "2_2") (pintype "passive"))
      (node (ref "T4") (pin "2") (pinfunction "1C_PHY_2") (pintype "bidirectional"))
      (node (ref "T4") (pin "7") (pinfunction "2C_PHY_7") (pintype "bidirectional"))
    )
    (net (code "49") (name "Net-(T4-2C)") (class "Default")
      (node (ref "R65") (pin "2") (pinfunction "2_2") (pintype "passive"))
      (node (ref "T4") (pin "10") (pinfunction "2C_10") (pintype "bidirectional"))
    )
    (net (code "50") (name "Net-(U1-CEXT)") (class "Default")
      (node (ref "C7") (pin "1") (pinfunction "1_1") (pintype "passive"))
      (node (ref "U1") (pin "1") (pinfunction "DVDD_1.0_1") (pintype "bidirectional"))
      (node (ref "U1") (pin "2") (pinfunction "CEXT_2") (pintype "bidirectional"))
    )
    (net (code "51") (name "Net-(U1-MDC)") (class "Default")
      (node (ref "JP1") (pin "3") (pinfunction "3_3") (pintype "passive"))
      (node (ref "R16") (pin "1") (pinfunction "1_1") (pintype "passive"))
      (node (ref "U1") (pin "12") (pinfunction "MDC_12") (pintype "bidirectional"))
    )
    (net (code "52") (name "Net-(U1-MDIO)") (class "Default")
      (node (ref "JP1") (pin "4") (pinfunction "4_4") (pintype "passive"))
      (node (ref "R15") (pin "1") (pinfunction "1_1") (pintype "passive"))
      (node (ref "U1") (pin "11") (pinfunction "MDIO_11") (pintype "bidirectional"))
    )
    (net (code "53") (name "Net-(U1-PWDN{slash}INT)") (class "Default")
      (node (ref "R31") (pin "1") (pinfunction "1_1") (pintype "passive"))
      (node (ref "U1") (pin "21") (pinfunction "PWDN/INT_21") (pintype "bidirectional"))
    )
    (net (code "54") (name "Net-(U1-RX+)") (class "Default")
      (node (ref "R20") (pin "2") (pinfunction "2_2") (pintype "passive"))
      (node (ref "U1") (pin "5") (pinfunction "RX+_5") (pintype "bidirectional"))
    )
    (net (code "55") (name "Net-(U1-RX-)") (class "Default")
      (node (ref "R21") (pin "2") (pinfunction "2_2") (pintype "passive"))
      (node (ref "U1") (pin "6") (pinfunction "RX-_6") (pintype "bidirectional"))
    )
    (net (code "56") (name "Net-(U1-TX+)") (class "Default")
      (node (ref "R19") (pin "2") (pinfunction "2_2") (pintype "passive"))
      (node (ref "U1") (pin "4") (pinfunction "TX+_4") (pintype "bidirectional"))
    )
    (net (code "57") (name "Net-(U1-TX-)") (class "Default")
      (node (ref "R23") (pin "2") (pinfunction "2_2") (pintype "passive"))
      (node (ref "U1") (pin "7") (pinfunction "TX-_7") (pintype "bidirectional"))
    )
    (net (code "58") (name "Net-(U1-VDDA)") (class "Default")
      (node (ref "C1") (pin "1") (pinfunction "1_1") (pintype "passive"))
      (node (ref "C2") (pin "1") (pinfunction "1_1") (pintype "passive"))
      (node (ref "C26") (pin "1") (pinfunction "1_1") (pintype "passive"))
      (node (ref "C3") (pin "1") (pinfunction "1_1") (pintype "passive"))
      (node (ref "R1") (pin "1") (pinfunction "1_1") (pintype "passive"))
      (node (ref "U1") (pin "3") (pinfunction "VDDA_3") (pintype "bidirectional"))
    )
    (net (code "59") (name "Net-(U1-VDDIO)") (class "Default")
      (node (ref "C10") (pin "1") (pinfunction "1_1") (pintype "passive"))
      (node (ref "C4") (pin "1") (pinfunction "1_1") (pintype "passive"))
      (node (ref "C5") (pin "1") (pinfunction "1_1") (pintype "passive"))
      (node (ref "C6") (pin "1") (pinfunction "1_1") (pintype "passive"))
      (node (ref "R2") (pin "1") (pinfunction "1_1") (pintype "passive"))
      (node (ref "U1") (pin "17") (pinfunction "VDDIO_17") (pintype "bidirectional"))
    )
    (net (code "60") (name "Net-(U1-XI{slash}50M)") (class "Default")
      (node (ref "R44") (pin "1") (pinfunction "1_1") (pintype "passive"))
      (node (ref "R56") (pin "1") (pinfunction "1_1") (pintype "passive"))
      (node (ref "U1") (pin "10") (pinfunction "XI/50M_10") (pintype "bidirectional"))
    )
    (net (code "61") (name "Net-(U2-AVD)") (class "Default")
      (node (ref "C22") (pin "1") (pinfunction "1_1") (pintype "passive"))
      (node (ref "C23") (pin "1") (pinfunction "1_1") (pintype "passive"))
      (node (ref "C24") (pin "1") (pinfunction "1_1") (pintype "passive"))
      (node (ref "C25") (pin "1") (pinfunction "1_1") (pintype "passive"))
      (node (ref "R43") (pin "1") (pinfunction "1_1") (pintype "passive"))
      (node (ref "U2") (pin "14") (pinfunction "AVD_14") (pintype "bidirectional"))
    )
    (net (code "62") (name "Net-(U2-MDC)") (class "Default")
      (node (ref "JP2") (pin "3") (pinfunction "3_3") (pintype "passive"))
      (node (ref "R39") (pin "1") (pinfunction "1_1") (pintype "passive"))
      (node (ref "U2") (pin "20") (pinfunction "MDC_20") (pintype "bidirectional"))
    )
    (net (code "63") (name "Net-(U2-MDIO)") (class "Default")
      (node (ref "JP2") (pin "4") (pinfunction "4_4") (pintype "passive"))
      (node (ref "R38") (pin "1") (pinfunction "1_1") (pintype "passive"))
      (node (ref "U2") (pin "19") (pinfunction "MDIO_19") (pintype "bidirectional"))
    )
    (net (code "64") (name "Net-(U2-RBIAS)") (class "Default")
      (node (ref "R37") (pin "1") (pinfunction "1_1") (pintype "passive"))
      (node (ref "U2") (pin "16") (pinfunction "RBIAS_16") (pintype "bidirectional"))
    )
    (net (code "65") (name "Net-(U2-RX_CLK)") (class "Default")
      (node (ref "R14") (pin "2") (pinfunction "2_2") (pintype "passive"))
      (node (ref "U2") (pin "25") (pinfunction "RX_CLK_25") (pintype "bidirectional"))
    )
    (net (code "66") (name "Net-(U2-RX_DV{slash}RX_CTRL)") (class "Default")
      (node (ref "R12") (pin "2") (pinfunction "2_2") (pintype "passive"))
      (node (ref "U2") (pin "26") (pinfunction "RX_DV/RX_CTRL_26") (pintype "bidirectional"))
    )
    (net (code "67") (name "Net-(U2-TX_CLK)") (class "Default")
      (node (ref "R13") (pin "2") (pinfunction "2_2") (pintype "passive"))
      (node (ref "U2") (pin "2") (pinfunction "TX_CLK_2") (pintype "bidirectional"))
    )
    (net (code "68") (name "Net-(U2-TX_D0)") (class "Default")
      (node (ref "R3") (pin "2") (pinfunction "2_2") (pintype "passive"))
      (node (ref "U2") (pin "4") (pinfunction "TX_D0_4") (pintype "bidirectional"))
    )
    (net (code "69") (name "Net-(U2-TX_D1)") (class "Default")
      (node (ref "R4") (pin "2") (pinfunction "2_2") (pintype "passive"))
      (node (ref "U2") (pin "5") (pinfunction "TX_D1_5") (pintype "bidirectional"))
    )
    (net (code "70") (name "Net-(U2-TX_D2)") (class "Default")
      (node (ref "R5") (pin "2") (pinfunction "2_2") (pintype "passive"))
      (node (ref "U2") (pin "6") (pinfunction "TX_D2_6") (pintype "bidirectional"))
    )
    (net (code "71") (name "Net-(U2-TX_D3)") (class "Default")
      (node (ref "R6") (pin "2") (pinfunction "2_2") (pintype "passive"))
      (node (ref "U2") (pin "7") (pinfunction "TX_D3_7") (pintype "bidirectional"))
    )
    (net (code "72") (name "Net-(U2-TX_EN{slash}TX_CTRL)") (class "Default")
      (node (ref "R11") (pin "2") (pinfunction "2_2") (pintype "passive"))
      (node (ref "U2") (pin "3") (pinfunction "TX_EN/TX_CTRL_3") (pintype "bidirectional"))
    )
    (net (code "73") (name "Net-(U2-VDDIO)") (class "Default")
      (node (ref "C18") (pin "1") (pinfunction "1_1") (pintype "passive"))
      (node (ref "C19") (pin "1") (pinfunction "1_1") (pintype "passive"))
      (node (ref "C21") (pin "1") (pinfunction "1_1") (pintype "passive"))
      (node (ref "C27") (pin "1") (pinfunction "1_1") (pintype "passive"))
      (node (ref "R42") (pin "1") (pinfunction "1_1") (pintype "passive"))
      (node (ref "U2") (pin "21") (pinfunction "VDDIO_21") (pintype "bidirectional"))
    )
    (net (code "74") (name "Net-(U2-XI)") (class "Default")
      (node (ref "R45") (pin "2") (pinfunction "2_2") (pintype "passive"))
      (node (ref "U2") (pin "23") (pinfunction "XI_23") (pintype "bidirectional"))
    )
    (net (code "75") (name "Net-(U2-XO)") (class "Default")
      (node (ref "R56") (pin "2") (pinfunction "2_2") (pintype "passive"))
      (node (ref "U2") (pin "22") (pinfunction "XO_22") (pintype "bidirectional"))
    )
    (net (code "76") (name "Net-(U2-~{INT{slash}PWDN})") (class "Default")
      (node (ref "R40") (pin "1") (pinfunction "1_1") (pintype "passive"))
      (node (ref "U2") (pin "8") (pinfunction "~{INT/PWDN}_8") (pintype "bidirectional"))
    )
    (net (code "77") (name "Net-(U3-OUT)") (class "Default")
      (node (ref "R44") (pin "2") (pinfunction "2_2") (pintype "passive"))
      (node (ref "R45") (pin "1") (pinfunction "1_1") (pintype "passive"))
      (node (ref "U3") (pin "3") (pinfunction "OUT_3") (pintype "bidirectional"))
    )
    (net (code "78") (name "Net-(U3-VCC)") (class "Default")
      (node (ref "C28") (pin "1") (pinfunction "1_1") (pintype "passive"))
      (node (ref "R46") (pin "1") (pinfunction "1_1") (pintype "passive"))
      (node (ref "U3") (pin "4") (pinfunction "VCC_4") (pintype "bidirectional"))
    )
    (net (code "79") (name "Net-(U4-BOOT)") (class "Default")
      (node (ref "C54") (pin "1") (pinfunction "1_1") (pintype "passive"))
      (node (ref "U4") (pin "7") (pinfunction "BOOT_7") (pintype "bidirectional"))
    )
    (net (code "80") (name "Net-(U4-EN)") (class "Default")
      (node (ref "R66") (pin "2") (pinfunction "2_2") (pintype "passive"))
      (node (ref "U4") (pin "2") (pinfunction "EN_2") (pintype "bidirectional"))
    )
    (net (code "81") (name "Net-(U4-FB)") (class "Default")
      (node (ref "R68") (pin "1") (pinfunction "1_1") (pintype "passive"))
      (node (ref "R69") (pin "2") (pinfunction "2_2") (pintype "passive"))
      (node (ref "U4") (pin "5") (pinfunction "FB_5") (pintype "bidirectional"))
    )
    (net (code "82") (name "Net-(U4-RT)") (class "Default")
      (node (ref "R67") (pin "2") (pinfunction "2_2") (pintype "passive"))
      (node (ref "U4") (pin "4") (pinfunction "RT_4") (pintype "bidirectional"))
    )
    (net (code "83") (name "RST_N") (class "Default")
      (node (ref "U4") (pin "6") (pinfunction "PG_6") (pintype "bidirectional"))
    )
    (net (code "84") (name "RST_N-1") (class "Default")
      (node (ref "JP1") (pin "2") (pinfunction "2_2") (pintype "passive"))
      (node (ref "R18") (pin "1") (pinfunction "1_1") (pintype "passive"))
      (node (ref "U1") (pin "31") (pinfunction "~{RST_N}_31") (pintype "bidirectional"))
    )
    (net (code "85") (name "RST_N-2") (class "Default")
      (node (ref "JP2") (pin "2") (pinfunction "2_2") (pintype "passive"))
      (node (ref "R41") (pin "1") (pinfunction "1_1") (pintype "passive"))
      (node (ref "U2") (pin "18") (pinfunction "~{RESET\\}_18") (pintype "bidirectional"))
    )
    (net (code "86") (name "RX+") (class "Default")
      (node (ref "J2") (pin "3") (pinfunction "3_3") (pintype "bidirectional"))
      (node (ref "T4") (pin "9") (pinfunction "2N_9") (pintype "bidirectional"))
    )
    (net (code "87") (name "RX-") (class "Default")
      (node (ref "J2") (pin "6") (pinfunction "6_6") (pintype "bidirectional"))
      (node (ref "T4") (pin "11") (pinfunction "2P_11") (pintype "bidirectional"))
    )
    (net (code "88") (name "RX_CLK-1") (class "Default")
      (node (ref "R13") (pin "1") (pinfunction "1_1") (pintype "passive"))
      (node (ref "U1") (pin "19") (pinfunction "RX_CLK/50M_RMII_19") (pintype "bidirectional"))
    )
    (net (code "89") (name "RX_D0-1") (class "Default")
      (node (ref "R3") (pin "1") (pinfunction "1_1") (pintype "passive"))
      (node (ref "U1") (pin "16") (pinfunction "RX_D0_16") (pintype "bidirectional"))
    )
    (net (code "90") (name "RX_D0-2") (class "Default")
      (node (ref "R47") (pin "1") (pinfunction "1_1") (pintype "passive"))
      (node (ref "R48") (pin "2") (pinfunction "2_2") (pintype "passive"))
      (node (ref "R7") (pin "2") (pinfunction "2_2") (pintype "passive"))
      (node (ref "U2") (pin "30") (pinfunction "RX_D0_30") (pintype "bidirectional"))
    )
    (net (code "91") (name "RX_D1-1") (class "Default")
      (node (ref "R27") (pin "1") (pinfunction "1_1") (pintype "passive"))
      (node (ref "R4") (pin "1") (pinfunction "1_1") (pintype "passive"))
      (node (ref "U1") (pin "15") (pinfunction "RX_D1_15") (pintype "bidirectional"))
    )
    (net (code "92") (name "RX_D1-2") (class "Default")
      (node (ref "R49") (pin "1") (pinfunction "1_1") (pintype "passive"))
      (node (ref "R8") (pin "2") (pinfunction "2_2") (pintype "passive"))
      (node (ref "U2") (pin "31") (pinfunction "RX_D1_31") (pintype "bidirectional"))
    )
    (net (code "93") (name "RX_D2-1") (class "Default")
      (node (ref "R26") (pin "1") (pinfunction "1_1") (pintype "passive"))
      (node (ref "R5") (pin "1") (pinfunction "1_1") (pintype "passive"))
      (node (ref "U1") (pin "14") (pinfunction "RX_D2_14") (pintype "bidirectional"))
    )
    (net (code "94") (name "RX_D2-2") (class "Default")
      (node (ref "R9") (pin "2") (pinfunction "2_2") (pintype "passive"))
      (node (ref "U2") (pin "32") (pinfunction "RX_D2_32") (pintype "bidirectional"))
    )
    (net (code "95") (name "RX_D3-1") (class "Default")
      (node (ref "R6") (pin "1") (pinfunction "1_1") (pintype "passive"))
      (node (ref "U1") (pin "13") (pinfunction "RX_D3_13") (pintype "bidirectional"))
    )
    (net (code "96") (name "RX_D3-2") (class "Default")
      (node (ref "R10") (pin "2") (pinfunction "2_2") (pintype "passive"))
      (node (ref "R53") (pin "1") (pinfunction "1_1") (pintype "passive"))
      (node (ref "R54") (pin "2") (pinfunction "2_2") (pintype "passive"))
      (node (ref "U2") (pin "1") (pinfunction "RX_D3_1") (pintype "bidirectional"))
    )
    (net (code "97") (name "RX_DV-1") (class "Default")
      (node (ref "R11") (pin "1") (pinfunction "1_1") (pintype "passive"))
      (node (ref "R28") (pin "1") (pinfunction "1_1") (pintype "passive"))
      (node (ref "U1") (pin "18") (pinfunction "RX_DV/CRS_DV_18") (pintype "bidirectional"))
    )
    (net (code "98") (name "RX_ER-1") (class "Default")
      (node (ref "U1") (pin "20") (pinfunction "RX_ER_20") (pintype "bidirectional"))
    )
    (net (code "99") (name "RX_ER-2") (class "Default")
      (node (ref "R51") (pin "1") (pinfunction "1_1") (pintype "passive"))
      (node (ref "R52") (pin "2") (pinfunction "2_2") (pintype "passive"))
      (node (ref "U2") (pin "28") (pinfunction "RX_ER_28") (pintype "bidirectional"))
    )
    (net (code "100") (name "TX+") (class "Default")
      (node (ref "J2") (pin "1") (pinfunction "1_1") (pintype "bidirectional"))
      (node (ref "T4") (pin "16") (pinfunction "1P_16") (pintype "bidirectional"))
    )
    (net (code "101") (name "TX-") (class "Default")
      (node (ref "J2") (pin "2") (pinfunction "2_2") (pintype "bidirectional"))
      (node (ref "T4") (pin "14") (pinfunction "1N_14") (pintype "bidirectional"))
    )
    (net (code "102") (name "TX_CLK-1") (class "Default")
      (node (ref "R14") (pin "1") (pinfunction "1_1") (pintype "passive"))
      (node (ref "U1") (pin "22") (pinfunction "TX_CLK_22") (pintype "bidirectional"))
    )
    (net (code "103") (name "TX_D0-1") (class "Default")
      (node (ref "R7") (pin "1") (pinfunction "1_1") (pintype "passive"))
      (node (ref "U1") (pin "24") (pinfunction "TX_D0_24") (pintype "bidirectional"))
    )
    (net (code "104") (name "TX_D1-1") (class "Default")
      (node (ref "R8") (pin "1") (pinfunction "1_1") (pintype "passive"))
      (node (ref "U1") (pin "25") (pinfunction "TX_D1_25") (pintype "bidirectional"))
    )
    (net (code "105") (name "TX_D2-1") (class "Default")
      (node (ref "R9") (pin "1") (pinfunction "1_1") (pintype "passive"))
      (node (ref "U1") (pin "26") (pinfunction "TX_D2_26") (pintype "bidirectional"))
    )
    (net (code "106") (name "TX_D3-1") (class "Default")
      (node (ref "R10") (pin "1") (pinfunction "1_1") (pintype "passive"))
      (node (ref "U1") (pin "27") (pinfunction "TX_D3_27") (pintype "bidirectional"))
    )
    (net (code "107") (name "TX_EN-1") (class "Default")
      (node (ref "R12") (pin "1") (pinfunction "1_1") (pintype "passive"))
      (node (ref "U1") (pin "23") (pinfunction "TX_EN_23") (pintype "bidirectional"))
    )
    (net (code "108") (name "V+") (class "Default")
      (node (ref "C17") (pin "1") (pinfunction "1_1") (pintype "passive"))
      (node (ref "C38") (pin "1") (pinfunction "1_1") (pintype "passive"))
      (node (ref "C39") (pin "1") (pinfunction "1_1") (pintype "passive"))
      (node (ref "C40") (pin "1") (pinfunction "1_1") (pintype "passive"))
      (node (ref "C41") (pin "1") (pinfunction "1_1") (pintype "passive"))
      (node (ref "C42") (pin "1") (pinfunction "1_1") (pintype "passive"))
      (node (ref "C43") (pin "1") (pinfunction "1_1") (pintype "passive"))
      (node (ref "C44") (pin "1") (pinfunction "1_1") (pintype "passive"))
      (node (ref "C45") (pin "1") (pinfunction "1_1") (pintype "passive"))
      (node (ref "C46") (pin "1") (pinfunction "1_1") (pintype "passive"))
      (node (ref "C50") (pin "1") (pinfunction "1_1") (pintype "passive"))
      (node (ref "C51") (pin "1") (pinfunction "1_1") (pintype "passive"))
      (node (ref "C52") (pin "1") (pinfunction "1_1") (pintype "passive"))
      (node (ref "C53") (pin "1") (pinfunction "1_1") (pintype "passive"))
      (node (ref "CR4") (pin "C") (pinfunction "K_C") (pintype "bidirectional"))
      (node (ref "D3") (pin "K") (pinfunction "K_K") (pintype "bidirectional"))
      (node (ref "F1") (pin "2") (pinfunction "P$2_2") (pintype "bidirectional"))
      (node (ref "F2") (pin "2") (pinfunction "P$2_2") (pintype "bidirectional"))
      (node (ref "R66") (pin "1") (pinfunction "1_1") (pintype "passive"))
      (node (ref "TP4") (pin "P$1") (pinfunction "P$1_P$1") (pintype "bidirectional"))
      (node (ref "U4") (pin "3") (pinfunction "VIN_3") (pintype "bidirectional"))
    )
    (net (code "109") (name "unconnected-(J1-2DM-Pad2)") (class "Default")
      (node (ref "J1") (pin "2") (pinfunction "2DM_2") (pintype "bidirectional"))
    )
    (net (code "110") (name "unconnected-(J1-3DP-Pad3)") (class "Default")
      (node (ref "J1") (pin "3") (pinfunction "3DP_3") (pintype "bidirectional"))
    )
    (net (code "111") (name "unconnected-(J1-4ID-Pad4)") (class "Default")
      (node (ref "J1") (pin "4") (pinfunction "4ID_4") (pintype "bidirectional"))
    )
    (net (code "112") (name "unconnected-(U1-XO-Pad9)") (class "Default")
      (node (ref "U1") (pin "9") (pinfunction "XO_9") (pintype "bidirectional"))
    )
    (net (code "113") (name "unconnected-(U2-COL{slash}GPIO2-Pad29)") (class "Default")
      (node (ref "U2") (pin "29") (pinfunction "COL/GPIO2_29") (pintype "bidirectional"))
    )
    (net (code "114") (name "unconnected-(U2-LED1{slash}GPIO1-Pad24)") (class "Default")
      (node (ref "U2") (pin "24") (pinfunction "LED1/GPIO1_24") (pintype "bidirectional"))
    )
    (net (code "115") (name "unconnected-(U2-NC1-Pad13)") (class "Default")
      (node (ref "U2") (pin "13") (pinfunction "NC1_13") (pintype "bidirectional"))
    )
    (net (code "116") (name "unconnected-(U2-NC2-Pad15)") (class "Default")
      (node (ref "U2") (pin "15") (pinfunction "NC2_15") (pintype "bidirectional"))
    )
    (net (code "117") (name "unconnected-(U3-NC-Pad1)") (class "Default")
      (node (ref "U3") (pin "1") (pinfunction "NC_1") (pintype "bidirectional"))
    )
  )
)
